# 780-00019_Rev1_Pg1_OLD.net
KiCad netlist of a schematic drawn in Altium Designer
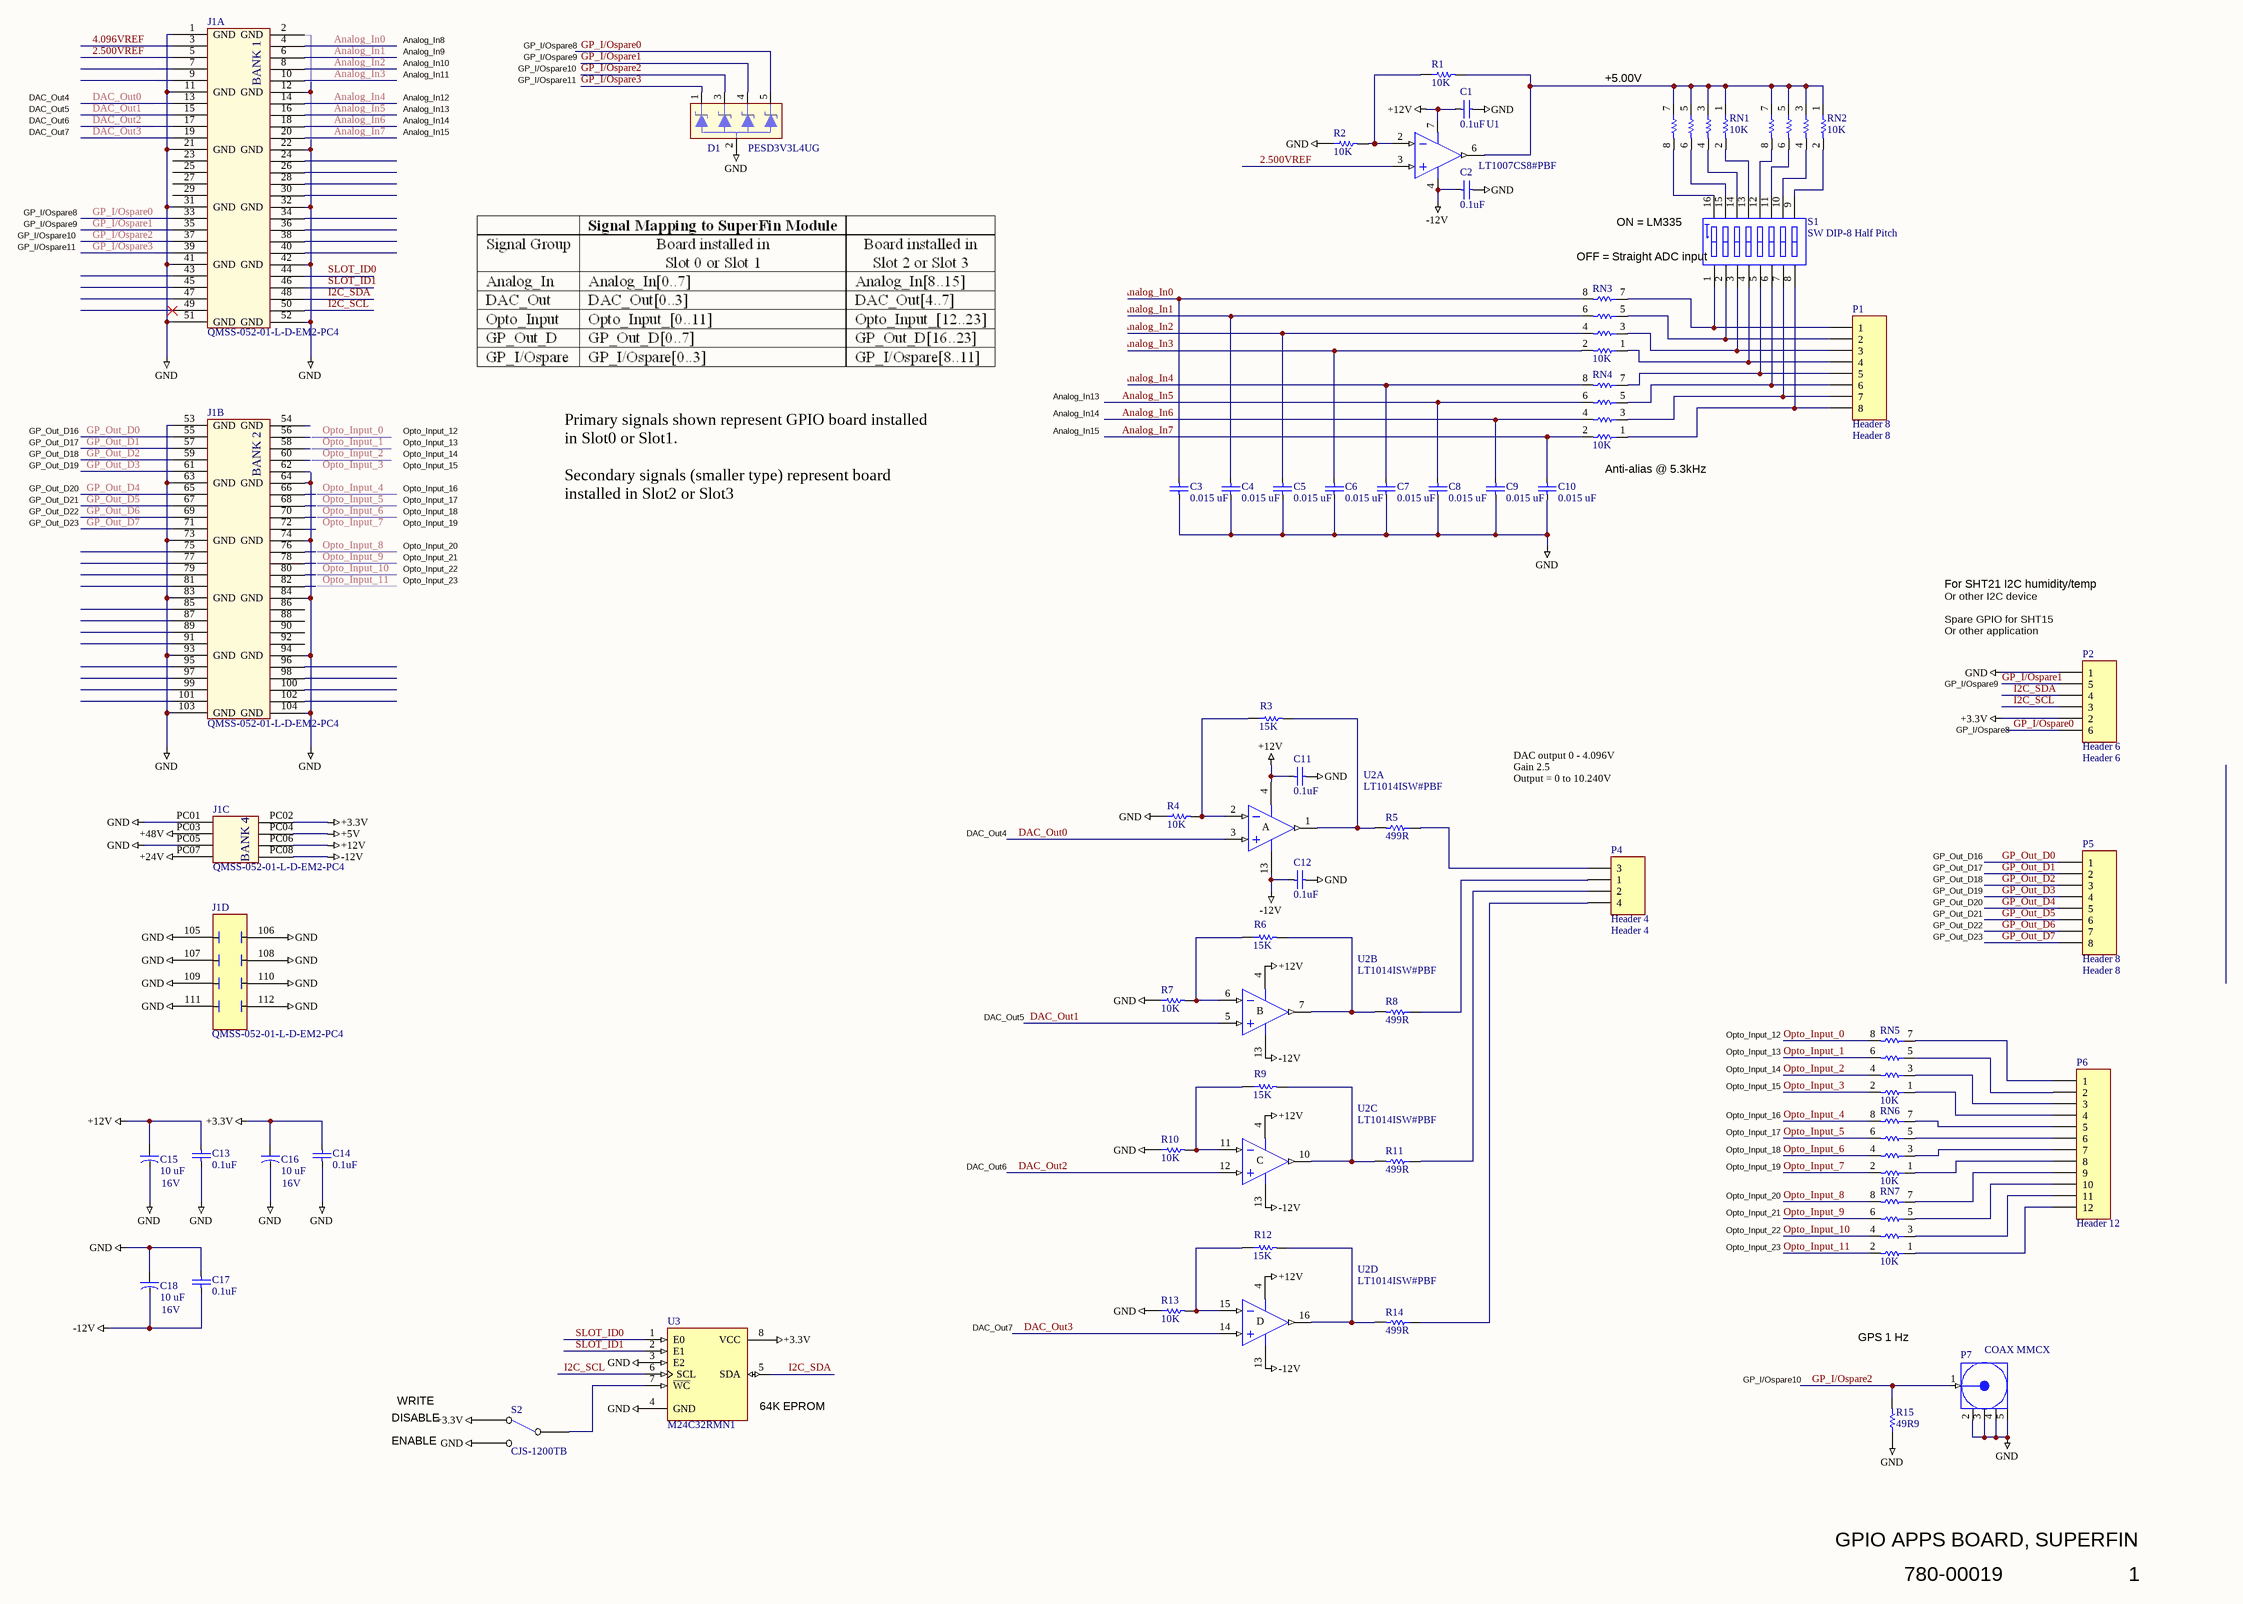
[diagram p0: 780-00019 Rev1 Pg1_OLD.SchDoc]

(export (version "E")
  (design (tool "Eeschema 10.0.6"))
  (components
    (comp (ref "C1")
      (value "0.1uF")
      (footprint "SMD_0805")
      (description "Capacitor")
      (fields (field (name "Comment") "Cap SMD"))
      (libsource (lib "Richs Schematic Components") (part "Cap SMD"))
    )
    (comp (ref "C2")
      (value "0.1uF")
      (footprint "SMD_0805")
      (description "Capacitor")
      (fields (field (name "Comment") "Cap SMD"))
      (libsource (lib "Richs Schematic Components") (part "Cap SMD"))
    )
    (comp (ref "C3")
      (value "0.015 uF")
      (footprint "SMD_0805")
      (description "Capacitor NP0")
      (fields (field (name "MANUFACTURER") "Murata") (field (name "Comment") "Cap SMD"))
      (libsource (lib "Richs Schematic Components") (part "Cap SMD"))
    )
    (comp (ref "C4")
      (value "0.015 uF")
      (footprint "SMD_0805")
      (description "Capacitor NP0")
      (fields (field (name "MANUFACTURER") "Murata") (field (name "Comment") "Cap SMD"))
      (libsource (lib "Richs Schematic Components") (part "Cap SMD"))
    )
    (comp (ref "C5")
      (value "0.015 uF")
      (footprint "SMD_0805")
      (description "Capacitor NP0")
      (fields (field (name "MANUFACTURER") "Murata") (field (name "Comment") "Cap SMD"))
      (libsource (lib "Richs Schematic Components") (part "Cap SMD"))
    )
    (comp (ref "C6")
      (value "0.015 uF")
      (footprint "SMD_0805")
      (description "Capacitor NP0")
      (fields (field (name "MANUFACTURER") "Murata") (field (name "Comment") "Cap SMD"))
      (libsource (lib "Richs Schematic Components") (part "Cap SMD"))
    )
    (comp (ref "C7")
      (value "0.015 uF")
      (footprint "SMD_0805")
      (description "Capacitor NP0")
      (fields (field (name "MANUFACTURER") "Murata") (field (name "Comment") "Cap SMD"))
      (libsource (lib "Richs Schematic Components") (part "Cap SMD"))
    )
    (comp (ref "C8")
      (value "0.015 uF")
      (footprint "SMD_0805")
      (description "Capacitor NP0")
      (fields (field (name "MANUFACTURER") "Murata") (field (name "Comment") "Cap SMD"))
      (libsource (lib "Richs Schematic Components") (part "Cap SMD"))
    )
    (comp (ref "C9")
      (value "0.015 uF")
      (footprint "SMD_0805")
      (description "Capacitor NP0")
      (fields (field (name "MANUFACTURER") "Murata") (field (name "Comment") "Cap SMD"))
      (libsource (lib "Richs Schematic Components") (part "Cap SMD"))
    )
    (comp (ref "C10")
      (value "0.015 uF")
      (footprint "SMD_0805")
      (description "Capacitor NP0")
      (fields (field (name "MANUFACTURER") "Murata") (field (name "Comment") "Cap SMD"))
      (libsource (lib "Richs Schematic Components") (part "Cap SMD"))
    )
    (comp (ref "C11")
      (value "0.1uF")
      (footprint "SMD_0805")
      (description "Capacitor")
      (fields (field (name "Comment") "Cap SMD"))
      (libsource (lib "Richs Schematic Components") (part "Cap SMD"))
    )
    (comp (ref "C12")
      (value "0.1uF")
      (footprint "SMD_0805")
      (description "Capacitor")
      (fields (field (name "Comment") "Cap SMD"))
      (libsource (lib "Richs Schematic Components") (part "Cap SMD"))
    )
    (comp (ref "C13")
      (value "0.1uF")
      (footprint "SMD_0805")
      (description "Capacitor")
      (fields (field (name "Comment") "Cap SMD"))
      (libsource (lib "Richs Schematic Components") (part "Cap SMD"))
    )
    (comp (ref "C14")
      (value "0.1uF")
      (footprint "SMD_0805")
      (description "Capacitor")
      (fields (field (name "Comment") "Cap SMD"))
      (libsource (lib "Richs Schematic Components") (part "Cap SMD"))
    )
    (comp (ref "C15")
      (value "16V")
      (footprint "SMD_CAP_3216")
      (description "outline 3.2mm x 1.6mm")
      (fields (field (name "MANUFACTURER") "KEMET") (field (name "ALTIUM_VALUE") "10 uF"))
      (libsource (lib "Richs Schematic Components") (part "Cap Tant 16V"))
    )
    (comp (ref "C16")
      (value "16V")
      (footprint "SMD_CAP_3216")
      (description "outline 3.2mm x 1.6mm")
      (fields (field (name "MANUFACTURER") "KEMET") (field (name "ALTIUM_VALUE") "10 uF"))
      (libsource (lib "Richs Schematic Components") (part "Cap Tant 16V"))
    )
    (comp (ref "C17")
      (value "0.1uF")
      (footprint "SMD_0805")
      (description "Capacitor")
      (fields (field (name "Comment") "Cap SMD"))
      (libsource (lib "Richs Schematic Components") (part "Cap SMD"))
    )
    (comp (ref "C18")
      (value "16V")
      (footprint "SMD_CAP_3216")
      (description "outline 3.2mm x 1.6mm")
      (fields (field (name "MANUFACTURER") "KEMET") (field (name "ALTIUM_VALUE") "10 uF"))
      (libsource (lib "Richs Schematic Components") (part "Cap Tant 16V"))
    )
    (comp (ref "D1")
      (value "PESD3V3L4UG")
      (footprint "SOT-353")
      (description "Quad ESD Diode 3.3V")
      (fields (field (name "MANUFACTURER") "NXP"))
      (libsource (lib "Richs Schematic Components") (part "ESD Diode 3.3V Quad"))
    )
    (comp (ref "J1")
      (value "QMSS-052-01-L-D-EM2-PC4")
      (footprint "QMS EDGE PWR PINS - 104 pin")
      (description "SAMTEC QMSS EDGE W/PWR PINS")
      (fields (field (name "MANUFACTURER") "SAMTEC") (field (name "Comment") "QMSS-EM-PC4-104pin"))
      (libsource (lib "Richs Schematic Components") (part "QMSS-EM-PC4-104pin"))
    )
    (comp (ref "P1")
      (value "Header 8")
      (footprint "HDR1X8 for IDC")
      (description "Header, 8-Pin")
      (fields (field (name "ALTIUM_VALUE") "Header 8"))
      (libsource (lib "Richs Schematic Components") (part "Header 8"))
    )
    (comp (ref "P2")
      (value "Header 6")
      (footprint "HDR1X6 for IDC")
      (description "Header, 6-Pin")
      (fields (field (name "ALTIUM_VALUE") "Header 6"))
      (libsource (lib "Richs Schematic Components") (part "Header 6"))
    )
    (comp (ref "P4")
      (value "Header 4")
      (footprint "HDR1X4 for IDC")
      (description "Header, 4-Pin")
      (fields (field (name "ALTIUM_VALUE") "Header 4"))
      (libsource (lib "Richs Schematic Components") (part "Header 4"))
    )
    (comp (ref "P5")
      (value "Header 8")
      (footprint "HDR1X8 for IDC")
      (description "Header, 8-Pin")
      (fields (field (name "ALTIUM_VALUE") "Header 8"))
      (libsource (lib "Richs Schematic Components") (part "Header 8"))
    )
    (comp (ref "P6")
      (value "Header 12")
      (footprint "HDR1X12 for IDC")
      (description "Header, 12-Pin")
      (fields (field (name "MANUFACTURER") "Tyco"))
      (libsource (lib "Richs Schematic Components") (part "Header 12"))
    )
    (comp (ref "P7")
      (value "COAX MMCX")
      (footprint "Miscellaneous Connectors:MMCX2.54-V5")
      (description "RF Coaxial PCB Connector, MMCX; Thru-Hole, Vertical Mount Plug,  50 Ohm Impedance")
      (fields (field (name "MANUFACTURER") "Emerson"))
      (libsource (lib "Richs Schematic Components") (part "COAX-M"))
    )
    (comp (ref "R1")
      (value "10K")
      (footprint "SMD_0805")
      (description "Resistor 0805")
      (fields (field (name "MANUFACTURER") "Vishay/Dale") (field (name "Comment") "Res 0805"))
      (libsource (lib "Richs Schematic Components") (part "Res SMD"))
    )
    (comp (ref "R2")
      (value "10K")
      (footprint "SMD_0805")
      (description "Resistor 0805")
      (fields (field (name "MANUFACTURER") "Vishay/Dale") (field (name "Comment") "Res 0805"))
      (libsource (lib "Richs Schematic Components") (part "Res SMD"))
    )
    (comp (ref "R3")
      (value "15K")
      (footprint "SMD_0805")
      (description "Resistor 0805")
      (fields (field (name "MANUFACTURER") "Vishay/Dale") (field (name "Comment") "Res 0805"))
      (libsource (lib "Richs Schematic Components") (part "Res SMD"))
    )
    (comp (ref "R4")
      (value "10K")
      (footprint "SMD_0805")
      (description "Resistor 0805")
      (fields (field (name "MANUFACTURER") "Vishay/Dale") (field (name "Comment") "Res 0805"))
      (libsource (lib "Richs Schematic Components") (part "Res SMD"))
    )
    (comp (ref "R5")
      (value "499R")
      (footprint "SMD_0805")
      (description "Resistor 0805")
      (fields (field (name "MANUFACTURER") "Vishay/Dale") (field (name "Comment") "Res 0805"))
      (libsource (lib "Richs Schematic Components") (part "Res SMD"))
    )
    (comp (ref "R6")
      (value "15K")
      (footprint "SMD_0805")
      (description "Resistor 0805")
      (fields (field (name "MANUFACTURER") "Vishay/Dale") (field (name "Comment") "Res 0805"))
      (libsource (lib "Richs Schematic Components") (part "Res SMD"))
    )
    (comp (ref "R7")
      (value "10K")
      (footprint "SMD_0805")
      (description "Resistor 0805")
      (fields (field (name "MANUFACTURER") "Vishay/Dale") (field (name "Comment") "Res 0805"))
      (libsource (lib "Richs Schematic Components") (part "Res SMD"))
    )
    (comp (ref "R8")
      (value "499R")
      (footprint "SMD_0805")
      (description "Resistor 0805")
      (fields (field (name "MANUFACTURER") "Vishay/Dale") (field (name "Comment") "Res 0805"))
      (libsource (lib "Richs Schematic Components") (part "Res SMD"))
    )
    (comp (ref "R9")
      (value "15K")
      (footprint "SMD_0805")
      (description "Resistor 0805")
      (fields (field (name "MANUFACTURER") "Vishay/Dale") (field (name "Comment") "Res 0805"))
      (libsource (lib "Richs Schematic Components") (part "Res SMD"))
    )
    (comp (ref "R10")
      (value "10K")
      (footprint "SMD_0805")
      (description "Resistor 0805")
      (fields (field (name "MANUFACTURER") "Vishay/Dale") (field (name "Comment") "Res 0805"))
      (libsource (lib "Richs Schematic Components") (part "Res SMD"))
    )
    (comp (ref "R11")
      (value "499R")
      (footprint "SMD_0805")
      (description "Resistor 0805")
      (fields (field (name "MANUFACTURER") "Vishay/Dale") (field (name "Comment") "Res 0805"))
      (libsource (lib "Richs Schematic Components") (part "Res SMD"))
    )
    (comp (ref "R12")
      (value "15K")
      (footprint "SMD_0805")
      (description "Resistor 0805")
      (fields (field (name "MANUFACTURER") "Vishay/Dale") (field (name "Comment") "Res 0805"))
      (libsource (lib "Richs Schematic Components") (part "Res SMD"))
    )
    (comp (ref "R13")
      (value "10K")
      (footprint "SMD_0805")
      (description "Resistor 0805")
      (fields (field (name "MANUFACTURER") "Vishay/Dale") (field (name "Comment") "Res 0805"))
      (libsource (lib "Richs Schematic Components") (part "Res SMD"))
    )
    (comp (ref "R14")
      (value "499R")
      (footprint "SMD_0805")
      (description "Resistor 0805")
      (fields (field (name "MANUFACTURER") "Vishay/Dale") (field (name "Comment") "Res 0805"))
      (libsource (lib "Richs Schematic Components") (part "Res SMD"))
    )
    (comp (ref "R15")
      (value "49R9")
      (footprint "SMD_0805")
      (description "Resistor 0805")
      (fields (field (name "MANUFACTURER") "Vishay/Dale") (field (name "Comment") "Res 0805"))
      (libsource (lib "Richs Schematic Components") (part "Res SMD"))
    )
    (comp (ref "RN1")
      (value "10K")
      (footprint "RES ARRAY 0603 x 4")
      (description "Resistor Array 4 Isolated")
      (fields (field (name "MANUFACTURER") "PANASONIC - ECG") (field (name "Comment") "RES ARRAY  x4 10K"))
      (libsource (lib "Richs Schematic Components") (part "RES ARRAY  x4 10K"))
    )
    (comp (ref "RN2")
      (value "10K")
      (footprint "RES ARRAY 0603 x 4")
      (description "Resistor Array 4 Isolated")
      (fields (field (name "MANUFACTURER") "PANASONIC - ECG") (field (name "Comment") "RES ARRAY  x4 10K"))
      (libsource (lib "Richs Schematic Components") (part "RES ARRAY  x4 10K"))
    )
    (comp (ref "RN3")
      (value "10K")
      (footprint "RES ARRAY 0603 x 4")
      (description "Resistor Array 4 Isolated")
      (fields (field (name "MANUFACTURER") "PANASONIC - ECG") (field (name "Comment") "RES ARRAY  x4 10K"))
      (libsource (lib "Richs Schematic Components") (part "RES ARRAY  x4 10K"))
    )
    (comp (ref "RN4")
      (value "10K")
      (footprint "RES ARRAY 0603 x 4")
      (description "Resistor Array 4 Isolated")
      (fields (field (name "MANUFACTURER") "PANASONIC - ECG") (field (name "Comment") "RES ARRAY  x4 10K"))
      (libsource (lib "Richs Schematic Components") (part "RES ARRAY  x4 10K"))
    )
    (comp (ref "RN5")
      (value "10K")
      (footprint "RES ARRAY 0603 x 4")
      (description "Resistor Array 4 Isolated")
      (fields (field (name "MANUFACTURER") "PANASONIC - ECG") (field (name "Comment") "RES ARRAY  x4 10K"))
      (libsource (lib "Richs Schematic Components") (part "RES ARRAY  x4 10K"))
    )
    (comp (ref "RN6")
      (value "10K")
      (footprint "RES ARRAY 0603 x 4")
      (description "Resistor Array 4 Isolated")
      (fields (field (name "MANUFACTURER") "PANASONIC - ECG") (field (name "Comment") "RES ARRAY  x4 10K"))
      (libsource (lib "Richs Schematic Components") (part "RES ARRAY  x4 10K"))
    )
    (comp (ref "RN7")
      (value "10K")
      (footprint "RES ARRAY 0603 x 4")
      (description "Resistor Array 4 Isolated")
      (fields (field (name "MANUFACTURER") "PANASONIC - ECG") (field (name "Comment") "RES ARRAY  x4 10K"))
      (libsource (lib "Richs Schematic Components") (part "RES ARRAY  x4 10K"))
    )
    (comp (ref "S1")
      (value "SW DIP-8 Half Pitch")
      (footprint "SW DIP 8 pos half pitch")
      (description "DIP Switch, 8 Position, SPST")
      (fields (field (name "MANUFACTURER") "GrayHill"))
      (libsource (lib "Richs Schematic Components") (part "SW DIP-8 Half Pitch"))
    )
    (comp (ref "S2")
      (value "CJS-1200TB")
      (footprint "CAS-120B")
      (fields (field (name "MANUFACTURER") "Copal Electronics"))
      (libsource (lib "JON_1_Library") (part "SW_SPDT_DOUG"))
    )
    (comp (ref "U1")
      (value "LT1007CS8#PBF")
      (footprint "S8_M")
      (description "Low Noise BJT input opamp")
      (fields (field (name "MANUFACTURER") "Linear Tech"))
      (libsource (lib "Richs Schematic Components") (part "LT1007CS8#PBF"))
    )
    (comp (ref "U2")
      (value "LT1014ISW#PBF")
      (footprint "SW16_N")
      (description "Quad Precision Operational Amplifier")
      (fields (field (name "MANUFACTURER") "Linear Tech"))
      (libsource (lib "LT Operational Amplifier") (part "LT1014ISW#PBF"))
    )
    (comp (ref "U3")
      (value "M24C32RMN1")
      (footprint "SOP8_N")
      (description "32 Kbit Serial I²C Bus EEPROM")
      (fields (field (name "MANUFACTURER") "ST Micro"))
      (libsource (lib "ST Memory EEPROM Serial") (part "M24C32RMN1"))
    )
  )
  (nets
    (net (code "1") (name "+3.3V") (class "Default")
      (node (ref "C14") (pin "1") (pinfunction "1_1") (pintype "passive"))
      (node (ref "C16") (pin "1") (pinfunction "1_1") (pintype "passive"))
      (node (ref "J1") (pin "PC02") (pinfunction "PC02_PC02") (pintype "passive"))
      (node (ref "P2") (pin "2") (pinfunction "2_2") (pintype "passive"))
      (node (ref "S2") (pin "3") (pinfunction "NC_3") (pintype "passive"))
      (node (ref "U3") (pin "8") (pinfunction "VCC_8") (pintype "power_in"))
    )
    (net (code "2") (name "+5V") (class "Default")
      (node (ref "J1") (pin "PC04") (pinfunction "PC04_PC04") (pintype "passive"))
    )
    (net (code "3") (name "+12V") (class "Default")
      (node (ref "C1") (pin "1") (pinfunction "1_1") (pintype "passive"))
      (node (ref "C11") (pin "1") (pinfunction "1_1") (pintype "passive"))
      (node (ref "C13") (pin "1") (pinfunction "1_1") (pintype "passive"))
      (node (ref "C15") (pin "1") (pinfunction "1_1") (pintype "passive"))
      (node (ref "J1") (pin "PC06") (pinfunction "PC06_PC06") (pintype "passive"))
      (node (ref "U1") (pin "7") (pinfunction "V+_7") (pintype "power_in"))
      (node (ref "U2") (pin "4") (pinfunction "V+_4") (pintype "power_in"))
    )
    (net (code "4") (name "+24V") (class "Default")
      (node (ref "J1") (pin "PC07") (pinfunction "PC07_PC07") (pintype "passive"))
    )
    (net (code "5") (name "+48V") (class "Default")
      (node (ref "J1") (pin "PC03") (pinfunction "PC03_PC03") (pintype "passive"))
    )
    (net (code "6") (name "-12V") (class "Default")
      (node (ref "C12") (pin "1") (pinfunction "1_1") (pintype "passive"))
      (node (ref "C17") (pin "2") (pinfunction "2_2") (pintype "passive"))
      (node (ref "C18") (pin "2") (pinfunction "2_2") (pintype "passive"))
      (node (ref "C2") (pin "1") (pinfunction "1_1") (pintype "passive"))
      (node (ref "J1") (pin "PC08") (pinfunction "PC08_PC08") (pintype "passive"))
      (node (ref "U1") (pin "4") (pinfunction "V-_4") (pintype "power_in"))
      (node (ref "U2") (pin "13") (pinfunction "V-_13") (pintype "power_in"))
    )
    (net (code "7") (name "/2.500VREF") (class "Default")
      (node (ref "J1") (pin "5") (pinfunction "5_5") (pintype "passive"))
      (node (ref "U1") (pin "3") (pinfunction "IN+_3") (pintype "input"))
    )
    (net (code "8") (name "/4.096VREF") (class "Default")
      (node (ref "J1") (pin "3") (pinfunction "3_3") (pintype "passive"))
    )
    (net (code "9") (name "/Analog_In0") (class "Default")
      (node (ref "C3") (pin "2") (pinfunction "2_2") (pintype "passive"))
      (node (ref "J1") (pin "4") (pinfunction "4_4") (pintype "passive"))
      (node (ref "RN3") (pin "8") (pinfunction "8_8") (pintype "passive"))
    )
    (net (code "10") (name "/Analog_In1") (class "Default")
      (node (ref "C4") (pin "2") (pinfunction "2_2") (pintype "passive"))
      (node (ref "J1") (pin "6") (pinfunction "6_6") (pintype "passive"))
      (node (ref "RN3") (pin "6") (pinfunction "6_6") (pintype "passive"))
    )
    (net (code "11") (name "/Analog_In2") (class "Default")
      (node (ref "C5") (pin "2") (pinfunction "2_2") (pintype "passive"))
      (node (ref "J1") (pin "8") (pinfunction "8_8") (pintype "passive"))
      (node (ref "RN3") (pin "4") (pinfunction "4_4") (pintype "passive"))
    )
    (net (code "12") (name "/Analog_In3") (class "Default")
      (node (ref "C6") (pin "2") (pinfunction "2_2") (pintype "passive"))
      (node (ref "J1") (pin "10") (pinfunction "10_10") (pintype "passive"))
      (node (ref "RN3") (pin "2") (pinfunction "2_2") (pintype "passive"))
    )
    (net (code "13") (name "/Analog_In4") (class "Default")
      (node (ref "C7") (pin "2") (pinfunction "2_2") (pintype "passive"))
      (node (ref "J1") (pin "14") (pinfunction "14_14") (pintype "passive"))
      (node (ref "RN4") (pin "8") (pinfunction "8_8") (pintype "passive"))
    )
    (net (code "14") (name "/Analog_In5") (class "Default")
      (node (ref "C8") (pin "2") (pinfunction "2_2") (pintype "passive"))
      (node (ref "J1") (pin "16") (pinfunction "16_16") (pintype "passive"))
      (node (ref "RN4") (pin "6") (pinfunction "6_6") (pintype "passive"))
    )
    (net (code "15") (name "/Analog_In6") (class "Default")
      (node (ref "C9") (pin "2") (pinfunction "2_2") (pintype "passive"))
      (node (ref "J1") (pin "18") (pinfunction "18_18") (pintype "passive"))
      (node (ref "RN4") (pin "4") (pinfunction "4_4") (pintype "passive"))
    )
    (net (code "16") (name "/Analog_In7") (class "Default")
      (node (ref "C10") (pin "2") (pinfunction "2_2") (pintype "passive"))
      (node (ref "J1") (pin "20") (pinfunction "20_20") (pintype "passive"))
      (node (ref "RN4") (pin "2") (pinfunction "2_2") (pintype "passive"))
    )
    (net (code "17") (name "/DAC_Out0") (class "Default")
      (node (ref "J1") (pin "13") (pinfunction "13_13") (pintype "passive"))
      (node (ref "U2") (pin "3") (pinfunction "IN+_3") (pintype "input"))
    )
    (net (code "18") (name "/DAC_Out1") (class "Default")
      (node (ref "J1") (pin "15") (pinfunction "15_15") (pintype "passive"))
      (node (ref "U2") (pin "5") (pinfunction "IN+_5") (pintype "input"))
    )
    (net (code "19") (name "/DAC_Out2") (class "Default")
      (node (ref "J1") (pin "17") (pinfunction "17_17") (pintype "passive"))
      (node (ref "U2") (pin "12") (pinfunction "IN+_12") (pintype "input"))
    )
    (net (code "20") (name "/DAC_Out3") (class "Default")
      (node (ref "J1") (pin "19") (pinfunction "19_19") (pintype "passive"))
      (node (ref "U2") (pin "14") (pinfunction "IN+_14") (pintype "input"))
    )
    (net (code "21") (name "/GP_I{slash}Ospare0") (class "Default")
      (node (ref "D1") (pin "5") (pintype "passive"))
      (node (ref "J1") (pin "33") (pinfunction "33_33") (pintype "passive"))
      (node (ref "P2") (pin "6") (pinfunction "6_6") (pintype "passive"))
    )
    (net (code "22") (name "/GP_I{slash}Ospare1") (class "Default")
      (node (ref "D1") (pin "4") (pintype "passive"))
      (node (ref "J1") (pin "35") (pinfunction "35_35") (pintype "passive"))
      (node (ref "P2") (pin "5") (pinfunction "5_5") (pintype "passive"))
    )
    (net (code "23") (name "/GP_I{slash}Ospare2") (class "Default")
      (node (ref "D1") (pin "3") (pintype "passive"))
      (node (ref "J1") (pin "37") (pinfunction "37_37") (pintype "passive"))
      (node (ref "P7") (pin "1") (pinfunction "Signal_1") (pintype "input"))
      (node (ref "R15") (pin "2") (pinfunction "2_2") (pintype "passive"))
    )
    (net (code "24") (name "/GP_I{slash}Ospare3") (class "Default")
      (node (ref "D1") (pin "1") (pintype "passive"))
      (node (ref "J1") (pin "39") (pinfunction "39_39") (pintype "passive"))
    )
    (net (code "25") (name "/GP_Out_D0") (class "Default")
      (node (ref "J1") (pin "55") (pinfunction "55_55") (pintype "passive"))
      (node (ref "P5") (pin "1") (pinfunction "1_1") (pintype "passive"))
    )
    (net (code "26") (name "/GP_Out_D1") (class "Default")
      (node (ref "J1") (pin "57") (pinfunction "57_57") (pintype "passive"))
      (node (ref "P5") (pin "2") (pinfunction "2_2") (pintype "passive"))
    )
    (net (code "27") (name "/GP_Out_D2") (class "Default")
      (node (ref "J1") (pin "59") (pinfunction "59_59") (pintype "passive"))
      (node (ref "P5") (pin "3") (pinfunction "3_3") (pintype "passive"))
    )
    (net (code "28") (name "/GP_Out_D3") (class "Default")
      (node (ref "J1") (pin "61") (pinfunction "61_61") (pintype "passive"))
      (node (ref "P5") (pin "4") (pinfunction "4_4") (pintype "passive"))
    )
    (net (code "29") (name "/GP_Out_D4") (class "Default")
      (node (ref "J1") (pin "65") (pinfunction "65_65") (pintype "passive"))
      (node (ref "P5") (pin "5") (pinfunction "5_5") (pintype "passive"))
    )
    (net (code "30") (name "/GP_Out_D5") (class "Default")
      (node (ref "J1") (pin "67") (pinfunction "67_67") (pintype "passive"))
      (node (ref "P5") (pin "6") (pinfunction "6_6") (pintype "passive"))
    )
    (net (code "31") (name "/GP_Out_D6") (class "Default")
      (node (ref "J1") (pin "69") (pinfunction "69_69") (pintype "passive"))
      (node (ref "P5") (pin "7") (pinfunction "7_7") (pintype "passive"))
    )
    (net (code "32") (name "/GP_Out_D7") (class "Default")
      (node (ref "J1") (pin "71") (pinfunction "71_71") (pintype "passive"))
      (node (ref "P5") (pin "8") (pinfunction "8_8") (pintype "passive"))
    )
    (net (code "33") (name "/I2C_SCL") (class "Default")
      (node (ref "J1") (pin "50") (pinfunction "50_50") (pintype "passive"))
      (node (ref "P2") (pin "3") (pinfunction "3_3") (pintype "passive"))
      (node (ref "U3") (pin "6") (pinfunction "SCL_6") (pintype "input"))
    )
    (net (code "34") (name "/I2C_SDA") (class "Default")
      (node (ref "J1") (pin "48") (pinfunction "48_48") (pintype "passive"))
      (node (ref "P2") (pin "4") (pinfunction "4_4") (pintype "passive"))
      (node (ref "U3") (pin "5") (pinfunction "SDA_5") (pintype "bidirectional"))
    )
    (net (code "35") (name "/Opto_Input_0") (class "Default")
      (node (ref "J1") (pin "56") (pinfunction "56_56") (pintype "passive"))
      (node (ref "RN5") (pin "8") (pinfunction "8_8") (pintype "passive"))
    )
    (net (code "36") (name "/Opto_Input_1") (class "Default")
      (node (ref "J1") (pin "58") (pinfunction "58_58") (pintype "passive"))
      (node (ref "RN5") (pin "6") (pinfunction "6_6") (pintype "passive"))
    )
    (net (code "37") (name "/Opto_Input_2") (class "Default")
      (node (ref "J1") (pin "60") (pinfunction "60_60") (pintype "passive"))
      (node (ref "RN5") (pin "4") (pinfunction "4_4") (pintype "passive"))
    )
    (net (code "38") (name "/Opto_Input_3") (class "Default")
      (node (ref "J1") (pin "62") (pinfunction "62_62") (pintype "passive"))
      (node (ref "RN5") (pin "2") (pinfunction "2_2") (pintype "passive"))
    )
    (net (code "39") (name "/Opto_Input_4") (class "Default")
      (node (ref "J1") (pin "66") (pinfunction "66_66") (pintype "passive"))
      (node (ref "RN6") (pin "8") (pinfunction "8_8") (pintype "passive"))
    )
    (net (code "40") (name "/Opto_Input_5") (class "Default")
      (node (ref "J1") (pin "68") (pinfunction "68_68") (pintype "passive"))
      (node (ref "RN6") (pin "6") (pinfunction "6_6") (pintype "passive"))
    )
    (net (code "41") (name "/Opto_Input_6") (class "Default")
      (node (ref "J1") (pin "70") (pinfunction "70_70") (pintype "passive"))
      (node (ref "RN6") (pin "4") (pinfunction "4_4") (pintype "passive"))
    )
    (net (code "42") (name "/Opto_Input_7") (class "Default")
      (node (ref "J1") (pin "72") (pinfunction "72_72") (pintype "passive"))
      (node (ref "RN6") (pin "2") (pinfunction "2_2") (pintype "passive"))
    )
    (net (code "43") (name "/Opto_Input_8") (class "Default")
      (node (ref "J1") (pin "76") (pinfunction "76_76") (pintype "passive"))
      (node (ref "RN7") (pin "8") (pinfunction "8_8") (pintype "passive"))
    )
    (net (code "44") (name "/Opto_Input_9") (class "Default")
      (node (ref "J1") (pin "78") (pinfunction "78_78") (pintype "passive"))
      (node (ref "RN7") (pin "6") (pinfunction "6_6") (pintype "passive"))
    )
    (net (code "45") (name "/Opto_Input_10") (class "Default")
      (node (ref "J1") (pin "80") (pinfunction "80_80") (pintype "passive"))
      (node (ref "RN7") (pin "4") (pinfunction "4_4") (pintype "passive"))
    )
    (net (code "46") (name "/Opto_Input_11") (class "Default")
      (node (ref "J1") (pin "82") (pinfunction "82_82") (pintype "passive"))
      (node (ref "RN7") (pin "2") (pinfunction "2_2") (pintype "passive"))
    )
    (net (code "47") (name "/SLOT_ID0") (class "Default")
      (node (ref "J1") (pin "44") (pinfunction "44_44") (pintype "passive"))
      (node (ref "U3") (pin "1") (pinfunction "E0_1") (pintype "input"))
    )
    (net (code "48") (name "/SLOT_ID1") (class "Default")
      (node (ref "J1") (pin "46") (pinfunction "46_46") (pintype "passive"))
      (node (ref "U3") (pin "2") (pinfunction "E1_2") (pintype "input"))
    )
    (net (code "49") (name "GND") (class "Default")
      (node (ref "C1") (pin "2") (pinfunction "2_2") (pintype "passive"))
      (node (ref "C10") (pin "1") (pinfunction "1_1") (pintype "passive"))
      (node (ref "C11") (pin "2") (pinfunction "2_2") (pintype "passive"))
      (node (ref "C12") (pin "2") (pinfunction "2_2") (pintype "passive"))
      (node (ref "C13") (pin "2") (pinfunction "2_2") (pintype "passive"))
      (node (ref "C14") (pin "2") (pinfunction "2_2") (pintype "passive"))
      (node (ref "C15") (pin "2") (pinfunction "2_2") (pintype "passive"))
      (node (ref "C16") (pin "2") (pinfunction "2_2") (pintype "passive"))
      (node (ref "C17") (pin "1") (pinfunction "1_1") (pintype "passive"))
      (node (ref "C18") (pin "1") (pinfunction "1_1") (pintype "passive"))
      (node (ref "C2") (pin "2") (pinfunction "2_2") (pintype "passive"))
      (node (ref "C3") (pin "1") (pinfunction "1_1") (pintype "passive"))
      (node (ref "C4") (pin "1") (pinfunction "1_1") (pintype "passive"))
      (node (ref "C5") (pin "1") (pinfunction "1_1") (pintype "passive"))
      (node (ref "C6") (pin "1") (pinfunction "1_1") (pintype "passive"))
      (node (ref "C7") (pin "1") (pinfunction "1_1") (pintype "passive"))
      (node (ref "C8") (pin "1") (pinfunction "1_1") (pintype "passive"))
      (node (ref "C9") (pin "1") (pinfunction "1_1") (pintype "passive"))
      (node (ref "D1") (pin "2") (pintype "passive"))
      (node (ref "J1") (pin "1") (pinfunction "GND_1") (pintype "passive"))
      (node (ref "J1") (pin "103") (pinfunction "GND_103") (pintype "passive"))
      (node (ref "J1") (pin "104") (pinfunction "GND_104") (pintype "passive"))
      (node (ref "J1") (pin "105") (pinfunction "GND_105") (pintype "passive"))
      (node (ref "J1") (pin "106") (pinfunction "GND_106") (pintype "passive"))
      (node (ref "J1") (pin "107") (pinfunction "GND_107") (pintype "passive"))
      (node (ref "J1") (pin "108") (pinfunction "GND_108") (pintype "passive"))
      (node (ref "J1") (pin "109") (pinfunction "GND_109") (pintype "passive"))
      (node (ref "J1") (pin "11") (pinfunction "GND_11") (pintype "passive"))
      (node (ref "J1") (pin "110") (pinfunction "GND_110") (pintype "passive"))
      (node (ref "J1") (pin "111") (pinfunction "GND_111") (pintype "passive"))
      (node (ref "J1") (pin "112") (pinfunction "GND_112") (pintype "passive"))
      (node (ref "J1") (pin "12") (pinfunction "GND_12") (pintype "passive"))
      (node (ref "J1") (pin "2") (pinfunction "GND_2") (pintype "passive"))
      (node (ref "J1") (pin "21") (pinfunction "GND_21") (pintype "passive"))
      (node (ref "J1") (pin "22") (pinfunction "GND_22") (pintype "passive"))
      (node (ref "J1") (pin "31") (pinfunction "GND_31") (pintype "passive"))
      (node (ref "J1") (pin "32") (pinfunction "GND_32") (pintype "passive"))
      (node (ref "J1") (pin "41") (pinfunction "GND_41") (pintype "passive"))
      (node (ref "J1") (pin "42") (pinfunction "GND_42") (pintype "passive"))
      (node (ref "J1") (pin "51") (pinfunction "GND_51") (pintype "passive"))
      (node (ref "J1") (pin "52") (pinfunction "GND_52") (pintype "passive"))
      (node (ref "J1") (pin "53") (pinfunction "GND_53") (pintype "passive"))
      (node (ref "J1") (pin "54") (pinfunction "GND_54") (pintype "passive"))
      (node (ref "J1") (pin "63") (pinfunction "GND_63") (pintype "passive"))
      (node (ref "J1") (pin "64") (pinfunction "GND_64") (pintype "passive"))
      (node (ref "J1") (pin "73") (pinfunction "GND_73") (pintype "passive"))
      (node (ref "J1") (pin "74") (pinfunction "GND_74") (pintype "passive"))
      (node (ref "J1") (pin "83") (pinfunction "GND_83") (pintype "passive"))
      (node (ref "J1") (pin "84") (pinfunction "GND_84") (pintype "passive"))
      (node (ref "J1") (pin "93") (pinfunction "GND_93") (pintype "passive"))
      (node (ref "J1") (pin "94") (pinfunction "GND_94") (pintype "passive"))
      (node (ref "J1") (pin "PC01") (pinfunction "PC01_PC01") (pintype "passive"))
      (node (ref "J1") (pin "PC05") (pinfunction "PC05_PC05") (pintype "passive"))
      (node (ref "P2") (pin "1") (pinfunction "1_1") (pintype "passive"))
      (node (ref "P7") (pin "2") (pinfunction "GND_2") (pintype "power_in"))
      (node (ref "P7") (pin "3") (pinfunction "GND_3") (pintype "power_in"))
      (node (ref "P7") (pin "4") (pinfunction "GND_4") (pintype "power_in"))
      (node (ref "P7") (pin "5") (pinfunction "GND_5") (pintype "power_in"))
      (node (ref "R10") (pin "1") (pinfunction "1_1") (pintype "passive"))
      (node (ref "R13") (pin "1") (pinfunction "1_1") (pintype "passive"))
      (node (ref "R15") (pin "1") (pinfunction "1_1") (pintype "passive"))
      (node (ref "R2") (pin "1") (pinfunction "1_1") (pintype "passive"))
      (node (ref "R4") (pin "1") (pinfunction "1_1") (pintype "passive"))
      (node (ref "R7") (pin "1") (pinfunction "1_1") (pintype "passive"))
      (node (ref "S2") (pin "1") (pinfunction "NO_1") (pintype "passive"))
      (node (ref "U3") (pin "3") (pinfunction "E2_3") (pintype "input"))
      (node (ref "U3") (pin "4") (pinfunction "GND_4") (pintype "power_in"))
    )
    (net (code "50") (name "Net-(P4-Pad1)") (class "Default")
      (node (ref "P4") (pin "1") (pinfunction "1_1") (pintype "passive"))
      (node (ref "R8") (pin "1") (pinfunction "1_1") (pintype "passive"))
    )
    (net (code "51") (name "Net-(P4-Pad2)") (class "Default")
      (node (ref "P4") (pin "2") (pinfunction "2_2") (pintype "passive"))
      (node (ref "R11") (pin "1") (pinfunction "1_1") (pintype "passive"))
    )
    (net (code "52") (name "Net-(P4-Pad3)") (class "Default")
      (node (ref "P4") (pin "3") (pinfunction "3_3") (pintype "passive"))
      (node (ref "R5") (pin "1") (pinfunction "1_1") (pintype "passive"))
    )
    (net (code "53") (name "Net-(P4-Pad4)") (class "Default")
      (node (ref "P4") (pin "4") (pinfunction "4_4") (pintype "passive"))
      (node (ref "R14") (pin "1") (pinfunction "1_1") (pintype "passive"))
    )
    (net (code "54") (name "Net-(P6-Pad1)") (class "Default")
      (node (ref "P6") (pin "1") (pinfunction "1_1") (pintype "passive"))
      (node (ref "RN5") (pin "7") (pinfunction "1_7") (pintype "passive"))
    )
    (net (code "55") (name "Net-(P6-Pad2)") (class "Default")
      (node (ref "P6") (pin "2") (pinfunction "2_2") (pintype "passive"))
      (node (ref "RN5") (pin "5") (pinfunction "5_5") (pintype "passive"))
    )
    (net (code "56") (name "Net-(P6-Pad3)") (class "Default")
      (node (ref "P6") (pin "3") (pinfunction "3_3") (pintype "passive"))
      (node (ref "RN5") (pin "3") (pinfunction "3_3") (pintype "passive"))
    )
    (net (code "57") (name "Net-(P6-Pad4)") (class "Default")
      (node (ref "P6") (pin "4") (pinfunction "4_4") (pintype "passive"))
      (node (ref "RN5") (pin "1") (pinfunction "1_1") (pintype "passive"))
    )
    (net (code "58") (name "Net-(P6-Pad5)") (class "Default")
      (node (ref "P6") (pin "5") (pinfunction "5_5") (pintype "passive"))
      (node (ref "RN6") (pin "7") (pinfunction "1_7") (pintype "passive"))
    )
    (net (code "59") (name "Net-(P6-Pad6)") (class "Default")
      (node (ref "P6") (pin "6") (pinfunction "6_6") (pintype "passive"))
      (node (ref "RN6") (pin "5") (pinfunction "5_5") (pintype "passive"))
    )
    (net (code "60") (name "Net-(P6-Pad7)") (class "Default")
      (node (ref "P6") (pin "7") (pinfunction "7_7") (pintype "passive"))
      (node (ref "RN6") (pin "3") (pinfunction "3_3") (pintype "passive"))
    )
    (net (code "61") (name "Net-(P6-Pad8)") (class "Default")
      (node (ref "P6") (pin "8") (pinfunction "8_8") (pintype "passive"))
      (node (ref "RN6") (pin "1") (pinfunction "1_1") (pintype "passive"))
    )
    (net (code "62") (name "Net-(P6-Pad9)") (class "Default")
      (node (ref "P6") (pin "9") (pinfunction "9_9") (pintype "passive"))
      (node (ref "RN7") (pin "7") (pinfunction "1_7") (pintype "passive"))
    )
    (net (code "63") (name "Net-(P6-Pad10)") (class "Default")
      (node (ref "P6") (pin "10") (pinfunction "10_10") (pintype "passive"))
      (node (ref "RN7") (pin "5") (pinfunction "5_5") (pintype "passive"))
    )
    (net (code "64") (name "Net-(P6-Pad11)") (class "Default")
      (node (ref "P6") (pin "11") (pinfunction "11_11") (pintype "passive"))
      (node (ref "RN7") (pin "3") (pinfunction "3_3") (pintype "passive"))
    )
    (net (code "65") (name "Net-(P6-Pad12)") (class "Default")
      (node (ref "P6") (pin "12") (pinfunction "12_12") (pintype "passive"))
      (node (ref "RN7") (pin "1") (pinfunction "1_1") (pintype "passive"))
    )
    (net (code "66") (name "Net-(S1-A1)") (class "Default")
      (node (ref "P1") (pin "1") (pinfunction "1_1") (pintype "passive"))
      (node (ref "RN3") (pin "7") (pinfunction "1_7") (pintype "passive"))
      (node (ref "S1") (pin "1") (pinfunction "A1_1") (pintype "passive"))
    )
    (net (code "67") (name "Net-(S1-A2)") (class "Default")
      (node (ref "P1") (pin "2") (pinfunction "2_2") (pintype "passive"))
      (node (ref "RN3") (pin "5") (pinfunction "5_5") (pintype "passive"))
      (node (ref "S1") (pin "2") (pinfunction "A2_2") (pintype "passive"))
    )
    (net (code "68") (name "Net-(S1-A3)") (class "Default")
      (node (ref "P1") (pin "3") (pinfunction "3_3") (pintype "passive"))
      (node (ref "RN3") (pin "3") (pinfunction "3_3") (pintype "passive"))
      (node (ref "S1") (pin "3") (pinfunction "A3_3") (pintype "passive"))
    )
    (net (code "69") (name "Net-(S1-A4)") (class "Default")
      (node (ref "P1") (pin "4") (pinfunction "4_4") (pintype "passive"))
      (node (ref "RN3") (pin "1") (pinfunction "1_1") (pintype "passive"))
      (node (ref "S1") (pin "4") (pinfunction "A4_4") (pintype "passive"))
    )
    (net (code "70") (name "Net-(S1-A5)") (class "Default")
      (node (ref "P1") (pin "5") (pinfunction "5_5") (pintype "passive"))
      (node (ref "RN4") (pin "7") (pinfunction "1_7") (pintype "passive"))
      (node (ref "S1") (pin "5") (pinfunction "A5_5") (pintype "passive"))
    )
    (net (code "71") (name "Net-(S1-A6)") (class "Default")
      (node (ref "P1") (pin "6") (pinfunction "6_6") (pintype "passive"))
      (node (ref "RN4") (pin "5") (pinfunction "5_5") (pintype "passive"))
      (node (ref "S1") (pin "6") (pinfunction "A6_6") (pintype "passive"))
    )
    (net (code "72") (name "Net-(S1-A7)") (class "Default")
      (node (ref "P1") (pin "7") (pinfunction "7_7") (pintype "passive"))
      (node (ref "RN4") (pin "3") (pinfunction "3_3") (pintype "passive"))
      (node (ref "S1") (pin "7") (pinfunction "A7_7") (pintype "passive"))
    )
    (net (code "73") (name "Net-(S1-A8)") (class "Default")
      (node (ref "P1") (pin "8") (pinfunction "8_8") (pintype "passive"))
      (node (ref "RN4") (pin "1") (pinfunction "1_1") (pintype "passive"))
      (node (ref "S1") (pin "8") (pinfunction "A8_8") (pintype "passive"))
    )
    (net (code "74") (name "Net-(S1-B1)") (class "Default")
      (node (ref "RN1") (pin "8") (pinfunction "8_8") (pintype "passive"))
      (node (ref "S1") (pin "16") (pinfunction "B1_16") (pintype "passive"))
    )
    (net (code "75") (name "Net-(S1-B2)") (class "Default")
      (node (ref "RN1") (pin "6") (pinfunction "6_6") (pintype "passive"))
      (node (ref "S1") (pin "15") (pinfunction "B2_15") (pintype "passive"))
    )
    (net (code "76") (name "Net-(S1-B3)") (class "Default")
      (node (ref "RN1") (pin "4") (pinfunction "4_4") (pintype "passive"))
      (node (ref "S1") (pin "14") (pinfunction "B3_14") (pintype "passive"))
    )
    (net (code "77") (name "Net-(S1-B4)") (class "Default")
      (node (ref "RN1") (pin "2") (pinfunction "2_2") (pintype "passive"))
      (node (ref "S1") (pin "13") (pinfunction "B4_13") (pintype "passive"))
    )
    (net (code "78") (name "Net-(S1-B5)") (class "Default")
      (node (ref "RN2") (pin "8") (pinfunction "8_8") (pintype "passive"))
      (node (ref "S1") (pin "12") (pinfunction "B5_12") (pintype "passive"))
    )
    (net (code "79") (name "Net-(S1-B6)") (class "Default")
      (node (ref "RN2") (pin "6") (pinfunction "6_6") (pintype "passive"))
      (node (ref "S1") (pin "11") (pinfunction "B6_11") (pintype "passive"))
    )
    (net (code "80") (name "Net-(S1-B7)") (class "Default")
      (node (ref "RN2") (pin "4") (pinfunction "4_4") (pintype "passive"))
      (node (ref "S1") (pin "10") (pinfunction "B7_10") (pintype "passive"))
    )
    (net (code "81") (name "Net-(S1-B8)") (class "Default")
      (node (ref "RN2") (pin "2") (pinfunction "2_2") (pintype "passive"))
      (node (ref "S1") (pin "9") (pinfunction "B8_9") (pintype "passive"))
    )
    (net (code "82") (name "Net-(S2-COM)") (class "Default")
      (node (ref "S2") (pin "2") (pinfunction "COM_2") (pintype "passive"))
      (node (ref "U3") (pin "7") (pinfunction "~{WC}_7") (pintype "input"))
    )
    (net (code "83") (name "Net-(U1-IN-)") (class "Default")
      (node (ref "R1") (pin "1") (pinfunction "1_1") (pintype "passive"))
      (node (ref "R2") (pin "2") (pinfunction "2_2") (pintype "passive"))
      (node (ref "U1") (pin "2") (pinfunction "IN-_2") (pintype "input"))
    )
    (net (code "84") (name "Net-(U1-OUT)") (class "Default")
      (node (ref "R1") (pin "2") (pinfunction "2_2") (pintype "passive"))
      (node (ref "RN1") (pin "1") (pinfunction "1_1") (pintype "passive"))
      (node (ref "RN1") (pin "3") (pinfunction "3_3") (pintype "passive"))
      (node (ref "RN1") (pin "5") (pinfunction "5_5") (pintype "passive"))
      (node (ref "RN1") (pin "7") (pinfunction "1_7") (pintype "passive"))
      (node (ref "RN2") (pin "1") (pinfunction "1_1") (pintype "passive"))
      (node (ref "RN2") (pin "3") (pinfunction "3_3") (pintype "passive"))
      (node (ref "RN2") (pin "5") (pinfunction "5_5") (pintype "passive"))
      (node (ref "RN2") (pin "7") (pinfunction "1_7") (pintype "passive"))
      (node (ref "U1") (pin "6") (pinfunction "OUT_6") (pintype "output"))
    )
    (net (code "85") (name "Net-(U2A-IN-)") (class "Default")
      (node (ref "R3") (pin "1") (pinfunction "1_1") (pintype "passive"))
      (node (ref "R4") (pin "2") (pinfunction "2_2") (pintype "passive"))
      (node (ref "U2") (pin "2") (pinfunction "IN-_2") (pintype "input"))
    )
    (net (code "86") (name "Net-(U2A-OUT)") (class "Default")
      (node (ref "R3") (pin "2") (pinfunction "2_2") (pintype "passive"))
      (node (ref "R5") (pin "2") (pinfunction "2_2") (pintype "passive"))
      (node (ref "U2") (pin "1") (pinfunction "OUT_1") (pintype "output"))
    )
    (net (code "87") (name "Net-(U2B-IN-)") (class "Default")
      (node (ref "R6") (pin "1") (pinfunction "1_1") (pintype "passive"))
      (node (ref "R7") (pin "2") (pinfunction "2_2") (pintype "passive"))
      (node (ref "U2") (pin "6") (pinfunction "IN-_6") (pintype "input"))
    )
    (net (code "88") (name "Net-(U2B-OUT)") (class "Default")
      (node (ref "R6") (pin "2") (pinfunction "2_2") (pintype "passive"))
      (node (ref "R8") (pin "2") (pinfunction "2_2") (pintype "passive"))
      (node (ref "U2") (pin "7") (pinfunction "OUT_7") (pintype "output"))
    )
    (net (code "89") (name "Net-(U2C-IN-)") (class "Default")
      (node (ref "R10") (pin "2") (pinfunction "2_2") (pintype "passive"))
      (node (ref "R9") (pin "1") (pinfunction "1_1") (pintype "passive"))
      (node (ref "U2") (pin "11") (pinfunction "IN-_11") (pintype "input"))
    )
    (net (code "90") (name "Net-(U2C-OUT)") (class "Default")
      (node (ref "R11") (pin "2") (pinfunction "2_2") (pintype "passive"))
      (node (ref "R9") (pin "2") (pinfunction "2_2") (pintype "passive"))
      (node (ref "U2") (pin "10") (pinfunction "OUT_10") (pintype "output"))
    )
    (net (code "91") (name "Net-(U2D-IN-)") (class "Default")
      (node (ref "R12") (pin "1") (pinfunction "1_1") (pintype "passive"))
      (node (ref "R13") (pin "2") (pinfunction "2_2") (pintype "passive"))
      (node (ref "U2") (pin "15") (pinfunction "IN-_15") (pintype "input"))
    )
    (net (code "92") (name "Net-(U2D-OUT)") (class "Default")
      (node (ref "R12") (pin "2") (pinfunction "2_2") (pintype "passive"))
      (node (ref "R14") (pin "2") (pinfunction "2_2") (pintype "passive"))
      (node (ref "U2") (pin "16") (pinfunction "OUT_16") (pintype "output"))
    )
    (net (code "93") (name "unconnected-(J1-Pad7)") (class "Default")
      (node (ref "J1") (pin "7") (pinfunction "7_7") (pintype "passive"))
    )
    (net (code "94") (name "unconnected-(J1-Pad9)") (class "Default")
      (node (ref "J1") (pin "9") (pinfunction "9_9") (pintype "passive"))
    )
    (net (code "95") (name "unconnected-(J1-Pad23)") (class "Default")
      (node (ref "J1") (pin "23") (pinfunction "23_23") (pintype "passive"))
    )
    (net (code "96") (name "unconnected-(J1-Pad24)") (class "Default")
      (node (ref "J1") (pin "24") (pinfunction "24_24") (pintype "passive"))
    )
    (net (code "97") (name "unconnected-(J1-Pad25)") (class "Default")
      (node (ref "J1") (pin "25") (pinfunction "25_25") (pintype "passive"))
    )
    (net (code "98") (name "unconnected-(J1-Pad26)") (class "Default")
      (node (ref "J1") (pin "26") (pinfunction "26_26") (pintype "passive"))
    )
    (net (code "99") (name "unconnected-(J1-Pad27)") (class "Default")
      (node (ref "J1") (pin "27") (pinfunction "27_27") (pintype "passive"))
    )
    (net (code "100") (name "unconnected-(J1-Pad28)") (class "Default")
      (node (ref "J1") (pin "28") (pinfunction "28_28") (pintype "passive"))
    )
    (net (code "101") (name "unconnected-(J1-Pad29)") (class "Default")
      (node (ref "J1") (pin "29") (pinfunction "29_29") (pintype "passive"))
    )
    (net (code "102") (name "unconnected-(J1-Pad30)") (class "Default")
      (node (ref "J1") (pin "30") (pinfunction "30_30") (pintype "passive"))
    )
    (net (code "103") (name "unconnected-(J1-Pad34)") (class "Default")
      (node (ref "J1") (pin "34") (pinfunction "34_34") (pintype "passive"))
    )
    (net (code "104") (name "unconnected-(J1-Pad36)") (class "Default")
      (node (ref "J1") (pin "36") (pinfunction "36_36") (pintype "passive"))
    )
    (net (code "105") (name "unconnected-(J1-Pad38)") (class "Default")
      (node (ref "J1") (pin "38") (pinfunction "38_38") (pintype "passive"))
    )
    (net (code "106") (name "unconnected-(J1-Pad40)") (class "Default")
      (node (ref "J1") (pin "40") (pinfunction "40_40") (pintype "passive"))
    )
    (net (code "107") (name "unconnected-(J1-Pad43)") (class "Default")
      (node (ref "J1") (pin "43") (pinfunction "43_43") (pintype "passive"))
    )
    (net (code "108") (name "unconnected-(J1-Pad45)") (class "Default")
      (node (ref "J1") (pin "45") (pinfunction "45_45") (pintype "passive"))
    )
    (net (code "109") (name "unconnected-(J1-Pad47)") (class "Default")
      (node (ref "J1") (pin "47") (pinfunction "47_47") (pintype "passive"))
    )
    (net (code "110") (name "unconnected-(J1-Pad49)") (class "Default")
      (node (ref "J1") (pin "49") (pinfunction "49_49") (pintype "passive+no_connect"))
    )
    (net (code "111") (name "unconnected-(J1-Pad75)") (class "Default")
      (node (ref "J1") (pin "75") (pinfunction "75_75") (pintype "passive"))
    )
    (net (code "112") (name "unconnected-(J1-Pad77)") (class "Default")
      (node (ref "J1") (pin "77") (pinfunction "77_77") (pintype "passive"))
    )
    (net (code "113") (name "unconnected-(J1-Pad79)") (class "Default")
      (node (ref "J1") (pin "79") (pinfunction "79_79") (pintype "passive"))
    )
    (net (code "114") (name "unconnected-(J1-Pad81)") (class "Default")
      (node (ref "J1") (pin "81") (pinfunction "81_81") (pintype "passive"))
    )
    (net (code "115") (name "unconnected-(J1-Pad85)") (class "Default")
      (node (ref "J1") (pin "85") (pinfunction "85_85") (pintype "passive"))
    )
    (net (code "116") (name "unconnected-(J1-Pad86)") (class "Default")
      (node (ref "J1") (pin "86") (pinfunction "86_86") (pintype "passive"))
    )
    (net (code "117") (name "unconnected-(J1-Pad87)") (class "Default")
      (node (ref "J1") (pin "87") (pinfunction "87_87") (pintype "passive"))
    )
    (net (code "118") (name "unconnected-(J1-Pad88)") (class "Default")
      (node (ref "J1") (pin "88") (pinfunction "88_88") (pintype "passive"))
    )
    (net (code "119") (name "unconnected-(J1-Pad89)") (class "Default")
      (node (ref "J1") (pin "89") (pinfunction "89_89") (pintype "passive"))
    )
    (net (code "120") (name "unconnected-(J1-Pad90)") (class "Default")
      (node (ref "J1") (pin "90") (pinfunction "90_90") (pintype "passive"))
    )
    (net (code "121") (name "unconnected-(J1-Pad91)") (class "Default")
      (node (ref "J1") (pin "91") (pinfunction "91_91") (pintype "passive"))
    )
    (net (code "122") (name "unconnected-(J1-Pad92)") (class "Default")
      (node (ref "J1") (pin "92") (pinfunction "92_92") (pintype "passive"))
    )
    (net (code "123") (name "unconnected-(J1-Pad95)") (class "Default")
      (node (ref "J1") (pin "95") (pinfunction "95_95") (pintype "passive"))
    )
    (net (code "124") (name "unconnected-(J1-Pad96)") (class "Default")
      (node (ref "J1") (pin "96") (pinfunction "96_96") (pintype "passive"))
    )
    (net (code "125") (name "unconnected-(J1-Pad97)") (class "Default")
      (node (ref "J1") (pin "97") (pinfunction "97_97") (pintype "passive"))
    )
    (net (code "126") (name "unconnected-(J1-Pad98)") (class "Default")
      (node (ref "J1") (pin "98") (pinfunction "98_98") (pintype "passive"))
    )
    (net (code "127") (name "unconnected-(J1-Pad99)") (class "Default")
      (node (ref "J1") (pin "99") (pinfunction "99_99") (pintype "passive"))
    )
    (net (code "128") (name "unconnected-(J1-Pad100)") (class "Default")
      (node (ref "J1") (pin "100") (pinfunction "100_100") (pintype "passive"))
    )
    (net (code "129") (name "unconnected-(J1-Pad101)") (class "Default")
      (node (ref "J1") (pin "101") (pinfunction "101_101") (pintype "passive"))
    )
    (net (code "130") (name "unconnected-(J1-Pad102)") (class "Default")
      (node (ref "J1") (pin "102") (pinfunction "102_102") (pintype "passive"))
    )
    (net (code "131") (name "unconnected-(U1-NC-Pad5)") (class "Default")
      (node (ref "U1") (pin "5") (pinfunction "NC_5") (pintype "passive"))
    )
    (net (code "132") (name "unconnected-(U1-VOSTRIM-Pad1)") (class "Default")
      (node (ref "U1") (pin "1") (pinfunction "VOSTRIM_1") (pintype "passive"))
    )
    (net (code "133") (name "unconnected-(U1-VOSTRIM-Pad8)") (class "Default")
      (node (ref "U1") (pin "8") (pinfunction "VOSTRIM_8") (pintype "passive"))
    )
  )
)
